# Diagnostics.net
KiCad netlist of a schematic drawn in Altium Designer
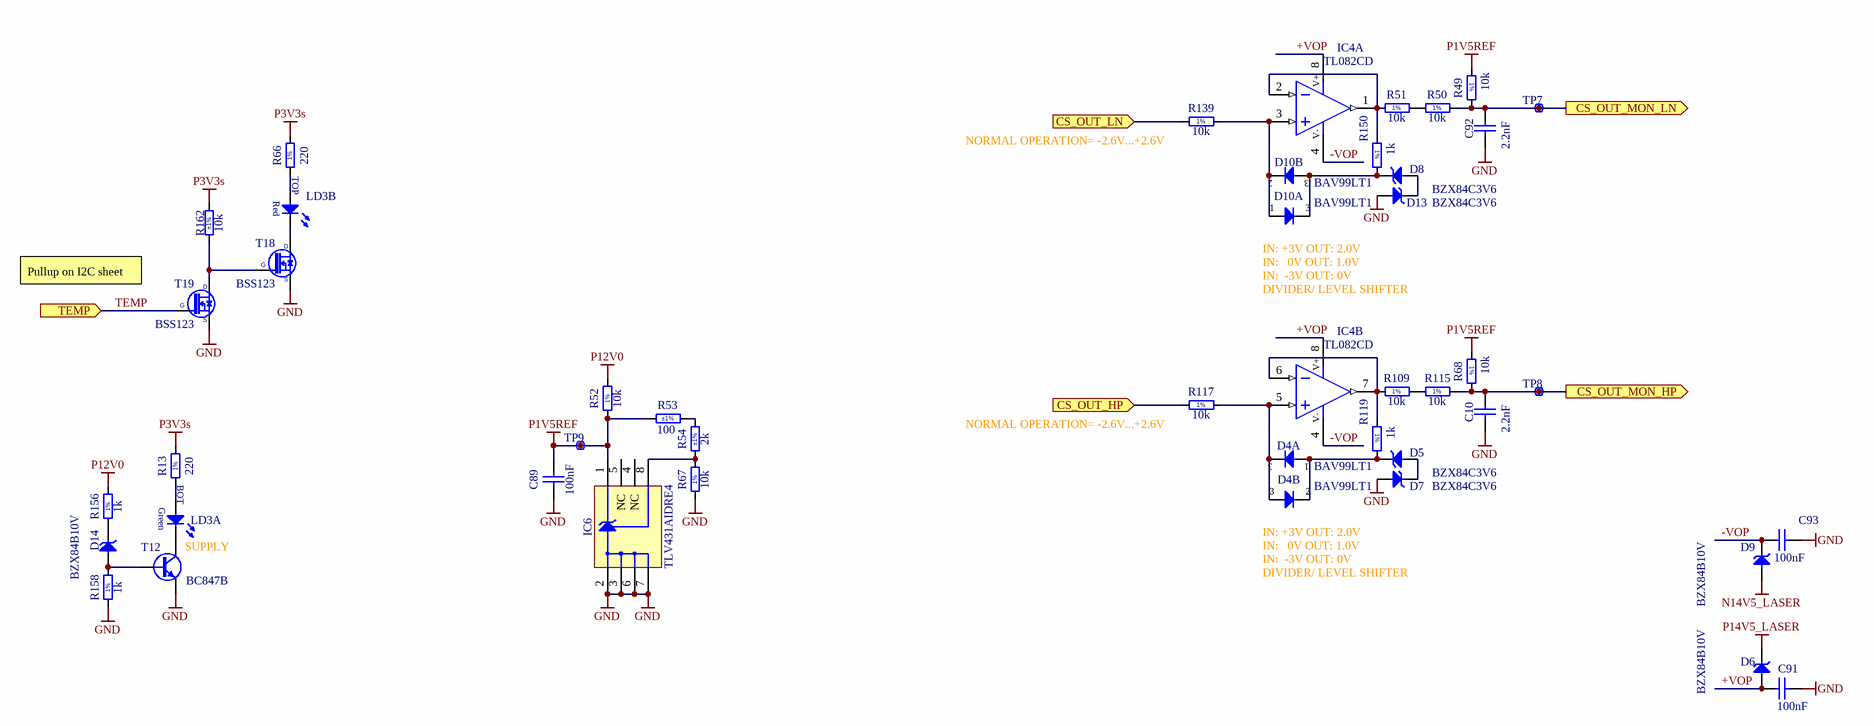
[diagram p0: Diagnostics.SchDoc]

(export (version "E")
  (design (tool "Eeschema 10.0.6"))
  (components
    (comp (ref "C10")
      (value "2.2nF")
      (footprint "CAPC1608X87N")
      (description "Non-polarised capacitor")
      (fields
        (field (name "PART NUMBER") "CC0603_2.2NF_50V_5%_C0G")
        (field (name "VOLTAGE") "50V")
        (field (name "AUTHOR") "CERN DEM JMW")
      )
      (libsource (lib "Capacitors") (part "Capacitor - non polarized"))
    )
    (comp (ref "C89")
      (value "100nF")
      (footprint "CAPC1608X87N")
      (description "Non-polarised capacitor")
      (fields
        (field (name "PART NUMBER") "CC0603_100NF_50V_10%_X7R")
        (field (name "VOLTAGE") "50V")
        (field (name "AUTHOR") "CERN DEM JLC")
      )
      (libsource (lib "Capacitors") (part "Capacitor - non polarized"))
    )
    (comp (ref "C91")
      (value "100nF")
      (footprint "CAPC1608X87N")
      (description "Non-polarised capacitor")
      (fields
        (field (name "PART NUMBER") "CC0603_100NF_50V_10%_X7R")
        (field (name "VOLTAGE") "50V")
        (field (name "AUTHOR") "CERN DEM JLC")
      )
      (libsource (lib "Capacitors") (part "Capacitor - non polarized"))
    )
    (comp (ref "C92")
      (value "2.2nF")
      (footprint "CAPC1608X87N")
      (description "Non-polarised capacitor")
      (fields
        (field (name "PART NUMBER") "CC0603_2.2NF_50V_5%_C0G")
        (field (name "VOLTAGE") "50V")
        (field (name "AUTHOR") "CERN DEM JMW")
      )
      (libsource (lib "Capacitors") (part "Capacitor - non polarized"))
    )
    (comp (ref "C93")
      (value "100nF")
      (footprint "CAPC1608X87N")
      (description "Non-polarised capacitor")
      (fields
        (field (name "PART NUMBER") "CC0603_100NF_50V_10%_X7R")
        (field (name "VOLTAGE") "50V")
        (field (name "AUTHOR") "CERN DEM JLC")
      )
      (libsource (lib "Capacitors") (part "Capacitor - non polarized"))
    )
    (comp (ref "D4")
      (value "BAV99LT1")
      (footprint "SOT95P240X110-3N")
      (description "Serial Diode")
      (fields
        (field (name "VOLTAGE") "70V")
        (field (name "POWER") "225mW")
        (field (name "AUTHOR") "CERN DEM JLC")
      )
      (libsource (lib "ICs And Semiconductors") (part "Diode x2 A1C3_A3C2"))
    )
    (comp (ref "D5")
      (value "BZX84C3V6")
      (footprint "SOT95P240X130-3N")
      (description "Diode Zener Anode Pin 1 Cathode Pin 3 (Pas de pin 2)")
      (fields
        (field (name "VOLTAGE") "3V6")
        (field (name "POWER") "350mW")
        (field (name "AUTHOR") "CERN DEM JLC")
      )
      (libsource (lib "ICs And Semiconductors") (part "Diode Zener A1C3"))
    )
    (comp (ref "D6")
      (value "BZX84B10V")
      (footprint "SOT95P248X115-3N")
      (description "Diode Zener Anode Pin 1 Cathode Pin 3 (Pas de pin 2)")
      (fields
        (field (name "VOLTAGE") "10V")
        (field (name "POWER") "300mW")
        (field (name "AUTHOR") "CERN DEM JLC")
      )
      (libsource (lib "ICs And Semiconductors") (part "Diode Zener A1C3"))
    )
    (comp (ref "D7")
      (value "BZX84C3V6")
      (footprint "SOT95P240X130-3N")
      (description "Diode Zener Anode Pin 1 Cathode Pin 3 (Pas de pin 2)")
      (fields
        (field (name "VOLTAGE") "3V6")
        (field (name "POWER") "350mW")
        (field (name "AUTHOR") "CERN DEM JLC")
      )
      (libsource (lib "ICs And Semiconductors") (part "Diode Zener A1C3"))
    )
    (comp (ref "D8")
      (value "BZX84C3V6")
      (footprint "SOT95P240X130-3N")
      (description "Diode Zener Anode Pin 1 Cathode Pin 3 (Pas de pin 2)")
      (fields
        (field (name "VOLTAGE") "3V6")
        (field (name "POWER") "350mW")
        (field (name "AUTHOR") "CERN DEM JLC")
      )
      (libsource (lib "ICs And Semiconductors") (part "Diode Zener A1C3"))
    )
    (comp (ref "D9")
      (value "BZX84B10V")
      (footprint "SOT95P248X115-3N")
      (description "Diode Zener Anode Pin 1 Cathode Pin 3 (Pas de pin 2)")
      (fields
        (field (name "VOLTAGE") "10V")
        (field (name "POWER") "300mW")
        (field (name "AUTHOR") "CERN DEM JLC")
      )
      (libsource (lib "ICs And Semiconductors") (part "Diode Zener A1C3"))
    )
    (comp (ref "D10")
      (value "BAV99LT1")
      (footprint "SOT95P240X110-3N")
      (description "Serial Diode")
      (fields
        (field (name "VOLTAGE") "70V")
        (field (name "POWER") "225mW")
        (field (name "AUTHOR") "CERN DEM JLC")
      )
      (libsource (lib "ICs And Semiconductors") (part "Diode x2 A1C3_A3C2"))
    )
    (comp (ref "D13")
      (value "BZX84C3V6")
      (footprint "SOT95P240X130-3N")
      (description "Diode Zener Anode Pin 1 Cathode Pin 3 (Pas de pin 2)")
      (fields
        (field (name "VOLTAGE") "3V6")
        (field (name "POWER") "350mW")
        (field (name "AUTHOR") "CERN DEM JLC")
      )
      (libsource (lib "ICs And Semiconductors") (part "Diode Zener A1C3"))
    )
    (comp (ref "D14")
      (value "BZX84B10V")
      (footprint "SOT95P248X115-3N")
      (description "Diode Zener Anode Pin 1 Cathode Pin 3 (Pas de pin 2)")
      (fields
        (field (name "VOLTAGE") "10V")
        (field (name "POWER") "300mW")
        (field (name "AUTHOR") "CERN DEM JLC")
      )
      (libsource (lib "ICs And Semiconductors") (part "Diode Zener A1C3"))
    )
    (comp (ref "IC4")
      (value "TL082CD")
      (footprint "SOIC127P600X175-8N")
      (description "Dual Operational Amplifier")
      (fields (field (name "MANUFACTURER") "TEXAS INSTRUMENTS") (field (name "AUTHOR") "CERN DEM JLC"))
      (libsource (lib "ICs And Semiconductors") (part "Operational Amplifier x2 Type1"))
    )
    (comp (ref "IC6")
      (value "TLV431AIDRE4")
      (footprint "SOIC127P600X175-8N")
      (description "Precision Programmable Reference")
      (fields (field (name "MANUFACTURER") "TEXAS INSTRUMENTS") (field (name "AUTHOR") "CERN DEM JLC"))
      (libsource (lib "ICs And Semiconductors") (part "TL431xD"))
    )
    (comp (ref "LD3")
      (value "Red/Green")
      (footprint "LED_DIALIGHT_571-0112F")
      (description "2x LED  Botom Green, Top Red")
      (fields
        (field (name "PART NUMBER") "LED_DIALIGHT_571-0112F")
        (field (name "MANUFACTURER") "DIALIGHT")
        (field (name "AUTHOR") "CERN DEM JLC")
      )
      (libsource (lib "ICs And Semiconductors") (part "LED x2 G-1C2A-BOT_R-3C4A-TOP"))
    )
    (comp (ref "R13")
      (value "220")
      (footprint "RESC1608X55N")
      (description "Resistor - 1%")
      (fields
        (field (name "PART NUMBER") "R0603_220R_1%_0.1W_100PPM")
        (field (name "POWER") "0.1W")
        (field (name "AUTHOR") "CERN DEM JLC")
      )
      (libsource (lib "Resistors") (part "Resistor - 1%"))
    )
    (comp (ref "R49")
      (value "10k")
      (footprint "RESC1608X55N")
      (description "Resistor - 1%")
      (fields
        (field (name "PART NUMBER") "R0603_10K_1%_0.1W_100PPM")
        (field (name "POWER") "0.1W")
        (field (name "AUTHOR") "CERN DEM JLC")
      )
      (libsource (lib "Resistors") (part "Resistor - 1%"))
    )
    (comp (ref "R50")
      (value "10k")
      (footprint "RESC1608X55N")
      (description "Resistor - 1%")
      (fields
        (field (name "PART NUMBER") "R0603_10K_1%_0.1W_100PPM")
        (field (name "POWER") "0.1W")
        (field (name "AUTHOR") "CERN DEM JLC")
      )
      (libsource (lib "Resistors") (part "Resistor - 1%"))
    )
    (comp (ref "R51")
      (value "10k")
      (footprint "RESC1608X55N")
      (description "Resistor - 1%")
      (fields
        (field (name "PART NUMBER") "R0603_10K_1%_0.1W_100PPM")
        (field (name "POWER") "0.1W")
        (field (name "AUTHOR") "CERN DEM JLC")
      )
      (libsource (lib "Resistors") (part "Resistor - 1%"))
    )
    (comp (ref "R52")
      (value "10k")
      (footprint "RESC1608X55N")
      (description "Resistor - 1%")
      (fields
        (field (name "PART NUMBER") "R0603_10K_1%_0.1W_100PPM")
        (field (name "POWER") "0.1W")
        (field (name "AUTHOR") "CERN DEM JLC")
      )
      (libsource (lib "Resistors") (part "Resistor - 1%"))
    )
    (comp (ref "R53")
      (value "100")
      (footprint "RESC1608X55N")
      (description "Resistor - 1%")
      (fields
        (field (name "TOLERANCE") "±1%")
        (field (name "PART NUMBER") "R0603_100R_1%_0.1W_100PPM")
        (field (name "POWER") "0.1W")
        (field (name "AUTHOR") "CERN DEM JLC")
      )
      (libsource (lib "Resistors") (part "Resistor - 1%"))
    )
    (comp (ref "R54")
      (value "2k")
      (footprint "RESC1608X55N")
      (description "Resistor - 1%")
      (fields
        (field (name "TOLERANCE") "±1%")
        (field (name "PART NUMBER") "R0603_2K_1%_0.1W_100PPM")
        (field (name "POWER") "0.1W")
        (field (name "AUTHOR") "CERN DEM JLC")
      )
      (libsource (lib "Resistors") (part "Resistor - 1%"))
    )
    (comp (ref "R66")
      (value "220")
      (footprint "RESC1608X55N")
      (description "Resistor - 1%")
      (fields
        (field (name "PART NUMBER") "R0603_220R_1%_0.1W_100PPM")
        (field (name "POWER") "0.1W")
        (field (name "AUTHOR") "CERN DEM JLC")
      )
      (libsource (lib "Resistors") (part "Resistor - 1%"))
    )
    (comp (ref "R67")
      (value "10k")
      (footprint "RESC1608X55N")
      (description "Resistor - 1%")
      (fields
        (field (name "PART NUMBER") "R0603_10K_1%_0.1W_100PPM")
        (field (name "POWER") "0.1W")
        (field (name "AUTHOR") "CERN DEM JLC")
      )
      (libsource (lib "Resistors") (part "Resistor - 1%"))
    )
    (comp (ref "R68")
      (value "10k")
      (footprint "RESC1608X55N")
      (description "Resistor - 1%")
      (fields
        (field (name "PART NUMBER") "R0603_10K_1%_0.1W_100PPM")
        (field (name "POWER") "0.1W")
        (field (name "AUTHOR") "CERN DEM JLC")
      )
      (libsource (lib "Resistors") (part "Resistor - 1%"))
    )
    (comp (ref "R109")
      (value "10k")
      (footprint "RESC1608X55N")
      (description "Resistor - 1%")
      (fields
        (field (name "PART NUMBER") "R0603_10K_1%_0.1W_100PPM")
        (field (name "POWER") "0.1W")
        (field (name "AUTHOR") "CERN DEM JLC")
      )
      (libsource (lib "Resistors") (part "Resistor - 1%"))
    )
    (comp (ref "R115")
      (value "10k")
      (footprint "RESC1608X55N")
      (description "Resistor - 1%")
      (fields
        (field (name "PART NUMBER") "R0603_10K_1%_0.1W_100PPM")
        (field (name "POWER") "0.1W")
        (field (name "AUTHOR") "CERN DEM JLC")
      )
      (libsource (lib "Resistors") (part "Resistor - 1%"))
    )
    (comp (ref "R117")
      (value "10k")
      (footprint "RESC1608X55N")
      (description "Resistor - 1%")
      (fields
        (field (name "PART NUMBER") "R0603_10K_1%_0.1W_100PPM")
        (field (name "POWER") "0.1W")
        (field (name "AUTHOR") "CERN DEM JLC")
      )
      (libsource (lib "Resistors") (part "Resistor - 1%"))
    )
    (comp (ref "R119")
      (value "1k")
      (footprint "RESC1608X55N")
      (description "Resistor - 1%")
      (fields
        (field (name "PART NUMBER") "R0603_1K_1%_0.1W_100PPM")
        (field (name "POWER") "0.1W")
        (field (name "AUTHOR") "CERN DEM JLC")
      )
      (libsource (lib "Resistors") (part "Resistor - 1%"))
    )
    (comp (ref "R139")
      (value "10k")
      (footprint "RESC1608X55N")
      (description "Resistor - 1%")
      (fields
        (field (name "PART NUMBER") "R0603_10K_1%_0.1W_100PPM")
        (field (name "POWER") "0.1W")
        (field (name "AUTHOR") "CERN DEM JLC")
      )
      (libsource (lib "Resistors") (part "Resistor - 1%"))
    )
    (comp (ref "R150")
      (value "1k")
      (footprint "RESC1608X55N")
      (description "Resistor - 1%")
      (fields
        (field (name "PART NUMBER") "R0603_1K_1%_0.1W_100PPM")
        (field (name "POWER") "0.1W")
        (field (name "AUTHOR") "CERN DEM JLC")
      )
      (libsource (lib "Resistors") (part "Resistor - 1%"))
    )
    (comp (ref "R156")
      (value "1k")
      (footprint "RESC1608X55N")
      (description "Resistor - 1%")
      (fields
        (field (name "PART NUMBER") "R0603_1K_1%_0.1W_100PPM")
        (field (name "POWER") "0.1W")
        (field (name "AUTHOR") "CERN DEM JLC")
      )
      (libsource (lib "Resistors") (part "Resistor - 1%"))
    )
    (comp (ref "R158")
      (value "1k")
      (footprint "RESC1608X55N")
      (description "Resistor - 1%")
      (fields
        (field (name "PART NUMBER") "R0603_1K_1%_0.1W_100PPM")
        (field (name "POWER") "0.1W")
        (field (name "AUTHOR") "CERN DEM JLC")
      )
      (libsource (lib "Resistors") (part "Resistor - 1%"))
    )
    (comp (ref "R162")
      (value "10k")
      (footprint "RESC1005X40N")
      (description "Resistor - 1%")
      (fields
        (field (name "TOLERANCE") "±1%")
        (field (name "PART NUMBER") "R0402_10K_1%_0.0625W_100PPM")
        (field (name "POWER") "0.0625W")
        (field (name "AUTHOR") "CERN DEM JLC")
      )
      (libsource (lib "") (part "Resistor - 1%_1"))
    )
    (comp (ref "T12")
      (value "BC847B")
      (footprint "SOT95P230X110-3N")
      (description "NPN Transistor")
      (fields (field (name "MANUFACTURER") "NXP SEMICONDUCTORS") (field (name "AUTHOR") "CERN DEM JLC"))
      (libsource (lib "ICs And Semiconductors") (part "NPN B1 E2 C3"))
    )
    (comp (ref "T18")
      (value "BSS123")
      (footprint "SOT95P240X130-3N")
      (description "N-CHANNEL MOSFET WITH DIODE")
      (fields (field (name "MANUFACTURER") "FAIRCHILD SEMICONDUCTOR") (field (name "AUTHOR") "CERN DEM JLC"))
      (libsource (lib "ICs And Semiconductors") (part "N-MOSFET-D 1G 2S 3D"))
    )
    (comp (ref "T19")
      (value "BSS123")
      (footprint "SOT95P240X130-3N")
      (description "N-CHANNEL MOSFET WITH DIODE")
      (fields (field (name "MANUFACTURER") "FAIRCHILD SEMICONDUCTOR") (field (name "AUTHOR") "CERN DEM JLC"))
      (libsource (lib "ICs And Semiconductors") (part "N-MOSFET-D 1G 2S 3D"))
    )
    (comp (ref "TP7")
      (value "Test Point")
      (footprint "TPS127")
      (fields (field (name "PART NUMBER") "SMD_PAD_1.27X1.27MM") (field (name "AUTHOR") "CERN DEM JLC"))
      (libsource (lib "Eletro-mechanical") (part "Test Point"))
    )
    (comp (ref "TP8")
      (value "Test Point")
      (footprint "TPS127")
      (fields (field (name "PART NUMBER") "SMD_PAD_1.27X1.27MM") (field (name "AUTHOR") "CERN DEM JLC"))
      (libsource (lib "Eletro-mechanical") (part "Test Point"))
    )
    (comp (ref "TP9")
      (value "Test Point")
      (footprint "TPS127")
      (fields (field (name "PART NUMBER") "SMD_PAD_1.27X1.27MM") (field (name "AUTHOR") "CERN DEM JLC"))
      (libsource (lib "Eletro-mechanical") (part "Test Point"))
    )
  )
  (nets
    (net (code "1") (name "/+VOP") (class "Default")
      (node (ref "C91") (pin "1") (pinfunction "1_1") (pintype "passive"))
      (node (ref "D6") (pin "1") (pinfunction "A_1") (pintype "passive"))
      (node (ref "IC4") (pin "8") (pinfunction "V+_8") (pintype "power_in"))
    )
    (net (code "2") (name "/-VOP") (class "Default")
      (node (ref "C93") (pin "1") (pinfunction "1_1") (pintype "passive"))
      (node (ref "D9") (pin "3") (pinfunction "C_3") (pintype "passive"))
      (node (ref "IC4") (pin "4") (pinfunction "V-_4") (pintype "power_in"))
    )
    (net (code "3") (name "/CS_OUT_HP") (class "Default")
      (node (ref "R117") (pin "1") (pinfunction "1_1") (pintype "passive"))
    )
    (net (code "4") (name "/CS_OUT_LN") (class "Default")
      (node (ref "R139") (pin "1") (pinfunction "1_1") (pintype "passive"))
    )
    (net (code "5") (name "/CS_OUT_MON_HP") (class "Default")
      (node (ref "C10") (pin "2") (pinfunction "2_2") (pintype "passive"))
      (node (ref "R115") (pin "2") (pinfunction "2_2") (pintype "passive"))
      (node (ref "R68") (pin "2") (pinfunction "2_2") (pintype "passive"))
      (node (ref "TP8") (pin "1") (pinfunction "1_1") (pintype "bidirectional"))
    )
    (net (code "6") (name "/CS_OUT_MON_LN") (class "Default")
      (node (ref "C92") (pin "2") (pinfunction "2_2") (pintype "passive"))
      (node (ref "R49") (pin "2") (pinfunction "2_2") (pintype "passive"))
      (node (ref "R50") (pin "2") (pinfunction "2_2") (pintype "passive"))
      (node (ref "TP7") (pin "1") (pinfunction "1_1") (pintype "bidirectional"))
    )
    (net (code "7") (name "/TEMP") (class "Default")
      (node (ref "T19") (pin "1") (pinfunction "G_1") (pintype "passive"))
    )
    (net (code "8") (name "GND") (class "Default")
      (node (ref "C10") (pin "1") (pinfunction "1_1") (pintype "passive"))
      (node (ref "C89") (pin "1") (pinfunction "1_1") (pintype "passive"))
      (node (ref "C91") (pin "2") (pinfunction "2_2") (pintype "passive"))
      (node (ref "C92") (pin "1") (pinfunction "1_1") (pintype "passive"))
      (node (ref "C93") (pin "2") (pinfunction "2_2") (pintype "passive"))
      (node (ref "D13") (pin "1") (pinfunction "A_1") (pintype "passive"))
      (node (ref "D7") (pin "1") (pinfunction "A_1") (pintype "passive"))
      (node (ref "IC6") (pin "2") (pinfunction "A_2") (pintype "passive"))
      (node (ref "IC6") (pin "3") (pinfunction "A_3") (pintype "passive"))
      (node (ref "IC6") (pin "6") (pinfunction "A_6") (pintype "passive"))
      (node (ref "IC6") (pin "7") (pinfunction "A_7") (pintype "passive"))
      (node (ref "R158") (pin "1") (pinfunction "1_1") (pintype "passive"))
      (node (ref "R67") (pin "1") (pinfunction "1_1") (pintype "passive"))
      (node (ref "T12") (pin "2") (pinfunction "E_2") (pintype "passive"))
      (node (ref "T18") (pin "2") (pinfunction "S_2") (pintype "passive"))
      (node (ref "T19") (pin "2") (pinfunction "S_2") (pintype "passive"))
    )
    (net (code "9") (name "N14V5_LASER") (class "Default")
      (node (ref "D9") (pin "1") (pinfunction "A_1") (pintype "passive"))
    )
    (net (code "10") (name "Net-(D4A-A)") (class "Default")
      (node (ref "D4") (pin "1") (pinfunction "A_1") (pintype "passive"))
      (node (ref "D4") (pin "2") (pinfunction "C_2") (pintype "passive"))
      (node (ref "D5") (pin "3") (pinfunction "C_3") (pintype "passive"))
      (node (ref "R119") (pin "2") (pinfunction "2_2") (pintype "passive"))
    )
    (net (code "11") (name "Net-(D4A-COMAC)") (class "Default")
      (node (ref "D4") (pin "3") (pinfunction "COMAC_3") (pintype "passive"))
      (node (ref "IC4") (pin "5") (pinfunction "IN+_5") (pintype "input"))
      (node (ref "R117") (pin "2") (pinfunction "2_2") (pintype "passive"))
    )
    (net (code "12") (name "Net-(D5-A)") (class "Default")
      (node (ref "D5") (pin "1") (pinfunction "A_1") (pintype "passive"))
      (node (ref "D7") (pin "3") (pinfunction "C_3") (pintype "passive"))
    )
    (net (code "13") (name "Net-(D10A-A)") (class "Default")
      (node (ref "D10") (pin "1") (pinfunction "A_1") (pintype "passive"))
      (node (ref "D10") (pin "2") (pinfunction "C_2") (pintype "passive"))
      (node (ref "IC4") (pin "3") (pinfunction "IN+_3") (pintype "input"))
      (node (ref "R139") (pin "2") (pinfunction "2_2") (pintype "passive"))
    )
    (net (code "14") (name "Net-(D10A-COMAC)") (class "Default")
      (node (ref "D10") (pin "3") (pinfunction "COMAC_3") (pintype "passive"))
      (node (ref "D8") (pin "3") (pinfunction "C_3") (pintype "passive"))
      (node (ref "R150") (pin "2") (pinfunction "2_2") (pintype "passive"))
    )
    (net (code "15") (name "Net-(D13-C)") (class "Default")
      (node (ref "D13") (pin "3") (pinfunction "C_3") (pintype "passive"))
      (node (ref "D8") (pin "1") (pinfunction "A_1") (pintype "passive"))
    )
    (net (code "16") (name "Net-(D14-A)") (class "Default")
      (node (ref "D14") (pin "1") (pinfunction "A_1") (pintype "passive"))
      (node (ref "R158") (pin "2") (pinfunction "2_2") (pintype "passive"))
      (node (ref "T12") (pin "1") (pinfunction "B_1") (pintype "passive"))
    )
    (net (code "17") (name "Net-(D14-C)") (class "Default")
      (node (ref "D14") (pin "3") (pinfunction "C_3") (pintype "passive"))
      (node (ref "R156") (pin "1") (pinfunction "1_1") (pintype "passive"))
    )
    (net (code "18") (name "Net-(IC4A-IN-)") (class "Default")
      (node (ref "IC4") (pin "1") (pinfunction "OUT_1") (pintype "output"))
      (node (ref "IC4") (pin "2") (pinfunction "IN-_2") (pintype "input"))
      (node (ref "R150") (pin "1") (pinfunction "1_1") (pintype "passive"))
      (node (ref "R51") (pin "1") (pinfunction "1_1") (pintype "passive"))
    )
    (net (code "19") (name "Net-(IC4B-IN-)") (class "Default")
      (node (ref "IC4") (pin "6") (pinfunction "IN-_6") (pintype "input"))
      (node (ref "IC4") (pin "7") (pinfunction "OUT_7") (pintype "output"))
      (node (ref "R109") (pin "1") (pinfunction "1_1") (pintype "passive"))
      (node (ref "R119") (pin "1") (pinfunction "1_1") (pintype "passive"))
    )
    (net (code "20") (name "Net-(IC6-REF)") (class "Default")
      (node (ref "IC6") (pin "8") (pinfunction "REF_8") (pintype "passive"))
      (node (ref "R54") (pin "1") (pinfunction "1_1") (pintype "passive"))
      (node (ref "R67") (pin "2") (pinfunction "2_2") (pintype "passive"))
    )
    (net (code "21") (name "Net-(LD3A-A)") (class "Default")
      (node (ref "LD3") (pin "2") (pinfunction "A_2") (pintype "passive"))
      (node (ref "R13") (pin "1") (pinfunction "1_1") (pintype "passive"))
    )
    (net (code "22") (name "Net-(LD3A-C)") (class "Default")
      (node (ref "LD3") (pin "1") (pinfunction "C_1") (pintype "passive"))
      (node (ref "T12") (pin "3") (pinfunction "C_3") (pintype "passive"))
    )
    (net (code "23") (name "Net-(LD3B-A)") (class "Default")
      (node (ref "LD3") (pin "4") (pinfunction "A_4") (pintype "passive"))
      (node (ref "R66") (pin "1") (pinfunction "1_1") (pintype "passive"))
    )
    (net (code "24") (name "Net-(LD3B-C)") (class "Default")
      (node (ref "LD3") (pin "3") (pinfunction "C_3") (pintype "passive"))
      (node (ref "T18") (pin "3") (pinfunction "D_3") (pintype "passive"))
    )
    (net (code "25") (name "Net-(R50-Pad1)") (class "Default")
      (node (ref "R50") (pin "1") (pinfunction "1_1") (pintype "passive"))
      (node (ref "R51") (pin "2") (pinfunction "2_2") (pintype "passive"))
    )
    (net (code "26") (name "Net-(R53-Pad1)") (class "Default")
      (node (ref "R53") (pin "1") (pinfunction "1_1") (pintype "passive"))
      (node (ref "R54") (pin "2") (pinfunction "2_2") (pintype "passive"))
    )
    (net (code "27") (name "Net-(R109-Pad2)") (class "Default")
      (node (ref "R109") (pin "2") (pinfunction "2_2") (pintype "passive"))
      (node (ref "R115") (pin "1") (pinfunction "1_1") (pintype "passive"))
    )
    (net (code "28") (name "Net-(T18-G)") (class "Default")
      (node (ref "R162") (pin "1") (pinfunction "1_1") (pintype "passive"))
      (node (ref "T18") (pin "1") (pinfunction "G_1") (pintype "passive"))
      (node (ref "T19") (pin "3") (pinfunction "D_3") (pintype "passive"))
    )
    (net (code "29") (name "P1V5REF") (class "Default")
      (node (ref "C89") (pin "2") (pinfunction "2_2") (pintype "passive"))
      (node (ref "IC6") (pin "1") (pinfunction "C_1") (pintype "passive"))
      (node (ref "R49") (pin "1") (pinfunction "1_1") (pintype "passive"))
      (node (ref "R52") (pin "1") (pinfunction "1_1") (pintype "passive"))
      (node (ref "R53") (pin "2") (pinfunction "2_2") (pintype "passive"))
      (node (ref "R68") (pin "1") (pinfunction "1_1") (pintype "passive"))
      (node (ref "TP9") (pin "1") (pinfunction "1_1") (pintype "bidirectional"))
    )
    (net (code "30") (name "P3V3s") (class "Default")
      (node (ref "R13") (pin "2") (pinfunction "2_2") (pintype "passive"))
      (node (ref "R162") (pin "2") (pinfunction "2_2") (pintype "passive"))
      (node (ref "R66") (pin "2") (pinfunction "2_2") (pintype "passive"))
    )
    (net (code "31") (name "P12V0") (class "Default")
      (node (ref "R156") (pin "2") (pinfunction "2_2") (pintype "passive"))
      (node (ref "R52") (pin "2") (pinfunction "2_2") (pintype "passive"))
    )
    (net (code "32") (name "P14V5_LASER") (class "Default")
      (node (ref "D6") (pin "3") (pinfunction "C_3") (pintype "passive"))
    )
    (net (code "33") (name "unconnected-(IC6-NC-Pad4)") (class "Default")
      (node (ref "IC6") (pin "4") (pinfunction "NC_4") (pintype "passive"))
    )
    (net (code "34") (name "unconnected-(IC6-NC-Pad5)") (class "Default")
      (node (ref "IC6") (pin "5") (pinfunction "NC_5") (pintype "passive"))
    )
  )
)
